# Power_Supply_2.net
KiCad netlist of a schematic drawn in Altium Designer
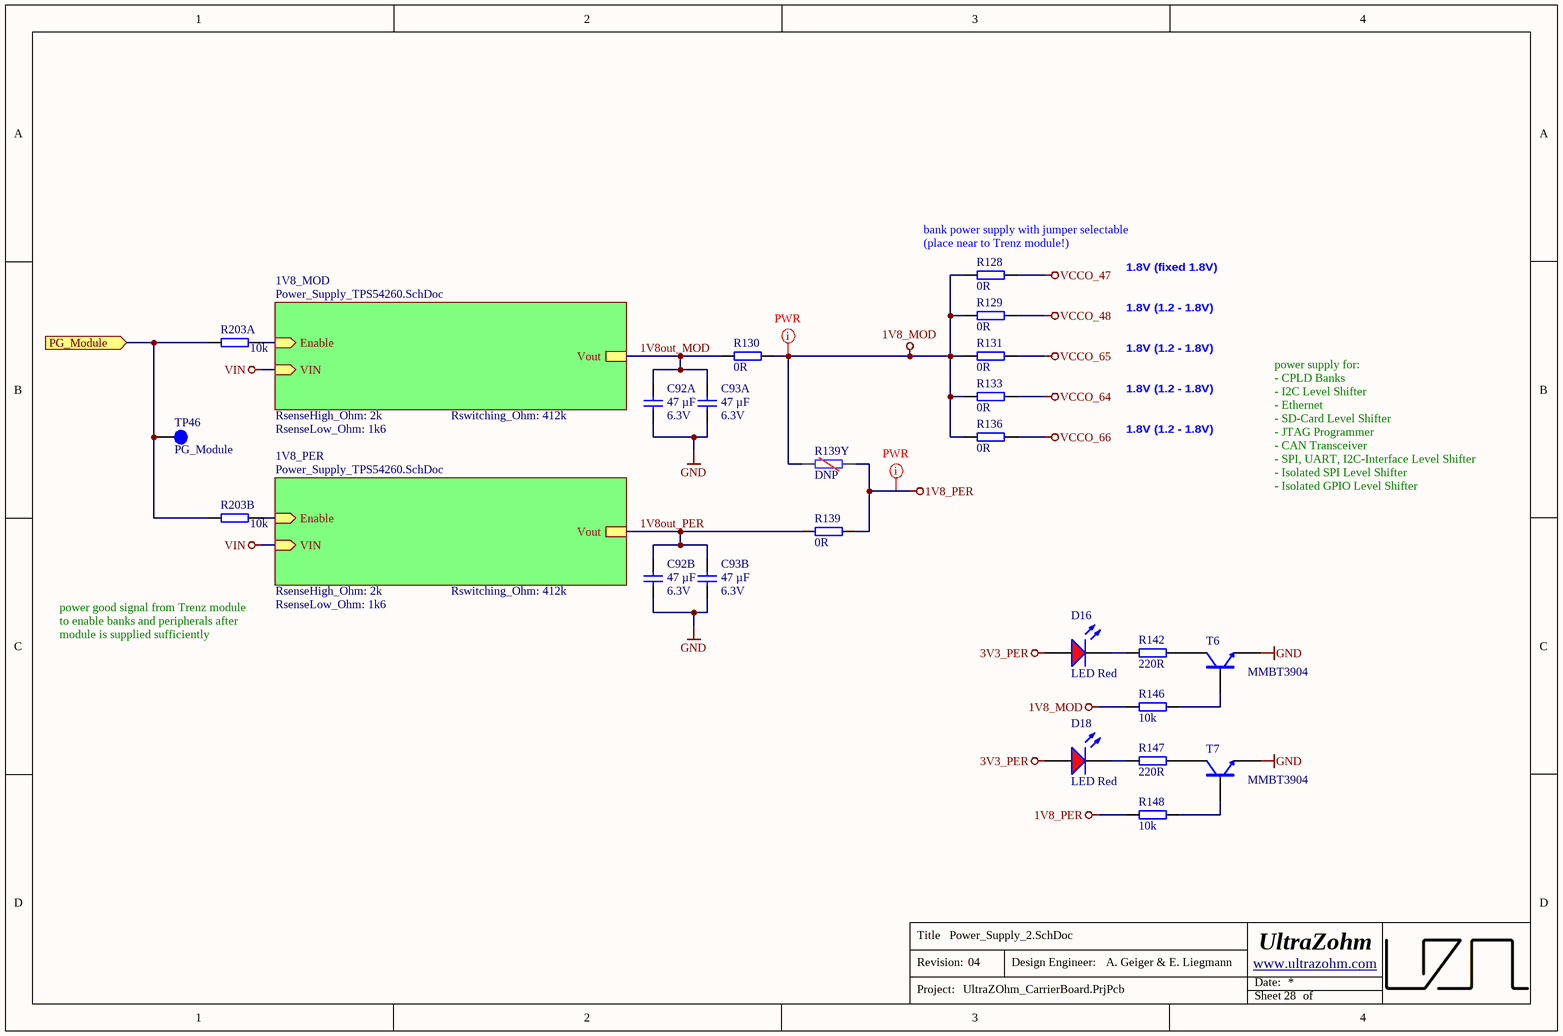
[diagram p0: Power_Supply_2.SchDoc]

(export (version "E")
  (design (tool "Eeschema 10.0.6"))
  (components
    (comp (ref "C92A")
      (value "47 µF")
      (footprint "C_0805_TE")
      (description "Generic capacitor")
      (fields
        (field (name "TOLERANCE") "10 %")
        (field (name "VOLTAGE") "6.3V")
        (field (name "MANUFACTURER PART NUMBER") "UZgen_C_0805_47uF_6.3V_X7R")
        (field (name "CREATED FROM") "UZgenTool")
      )
      (libsource (lib "user") (part "CAP-NP"))
    )
    (comp (ref "C92B")
      (value "47 µF")
      (footprint "C_0805_TE")
      (description "Generic capacitor")
      (fields
        (field (name "TOLERANCE") "10 %")
        (field (name "VOLTAGE") "6.3V")
        (field (name "MANUFACTURER PART NUMBER") "UZgen_C_0805_47uF_6.3V_X7R")
        (field (name "CREATED FROM") "UZgenTool")
      )
      (libsource (lib "user") (part "CAP-NP"))
    )
    (comp (ref "C93A")
      (value "47 µF")
      (footprint "C_0805_TE")
      (description "Generic capacitor")
      (fields
        (field (name "TOLERANCE") "10 %")
        (field (name "VOLTAGE") "6.3V")
        (field (name "MANUFACTURER PART NUMBER") "UZgen_C_0805_47uF_6.3V_X7R")
        (field (name "CREATED FROM") "UZgenTool")
      )
      (libsource (lib "user") (part "CAP-NP"))
    )
    (comp (ref "C93B")
      (value "47 µF")
      (footprint "C_0805_TE")
      (description "Generic capacitor")
      (fields
        (field (name "TOLERANCE") "10 %")
        (field (name "VOLTAGE") "6.3V")
        (field (name "MANUFACTURER PART NUMBER") "UZgen_C_0805_47uF_6.3V_X7R")
        (field (name "CREATED FROM") "UZgenTool")
      )
      (libsource (lib "user") (part "CAP-NP"))
    )
    (comp (ref "D16")
      (value "LED Red")
      (footprint "WL-SMCW_0603")
      (description "Standard LEDs - SMD 0603 red")
      (fields
        (field (name "MANUFACTURER PART NUMBER") "UZgen_LED_0603_Red")
        (field (name "MANUFACTURER") "UZgen")
        (field (name "CREATED FROM") "UZgenTool")
      )
      (libsource (lib "user") (part "LED_Red"))
    )
    (comp (ref "D18")
      (value "LED Red")
      (footprint "WL-SMCW_0603")
      (description "Standard LEDs - SMD 0603 red")
      (fields
        (field (name "MANUFACTURER PART NUMBER") "UZgen_LED_0603_Red")
        (field (name "MANUFACTURER") "UZgen")
        (field (name "CREATED FROM") "UZgenTool")
      )
      (libsource (lib "user") (part "LED_Red"))
    )
    (comp (ref "R128")
      (value "0R")
      (footprint "R_1206_TE")
      (description "Generic resistor")
      (fields
        (field (name "TOLERANCE") "1 %")
        (field (name "MANUFACTURER PART NUMBER") "UZgen_R_1206_0R")
        (field (name "CREATED FROM") "UZgenTool")
      )
      (libsource (lib "user") (part "RES"))
    )
    (comp (ref "R129")
      (value "0R")
      (footprint "R_1206_TE")
      (description "Generic resistor")
      (fields
        (field (name "TOLERANCE") "1 %")
        (field (name "MANUFACTURER PART NUMBER") "UZgen_R_1206_0R")
        (field (name "CREATED FROM") "UZgenTool")
      )
      (libsource (lib "user") (part "RES"))
    )
    (comp (ref "R130")
      (value "0R")
      (footprint "R_1206_TE")
      (description "Generic resistor")
      (fields
        (field (name "TOLERANCE") "1 %")
        (field (name "MANUFACTURER PART NUMBER") "UZgen_R_1206_0R")
        (field (name "CREATED FROM") "UZgenTool")
      )
      (libsource (lib "user") (part "RES"))
    )
    (comp (ref "R131")
      (value "0R")
      (footprint "R_1206_TE")
      (description "Generic resistor")
      (fields
        (field (name "TOLERANCE") "1 %")
        (field (name "MANUFACTURER PART NUMBER") "UZgen_R_1206_0R")
        (field (name "CREATED FROM") "UZgenTool")
      )
      (libsource (lib "user") (part "RES"))
    )
    (comp (ref "R133")
      (value "0R")
      (footprint "R_1206_TE")
      (description "Generic resistor")
      (fields
        (field (name "TOLERANCE") "1 %")
        (field (name "MANUFACTURER PART NUMBER") "UZgen_R_1206_0R")
        (field (name "CREATED FROM") "UZgenTool")
      )
      (libsource (lib "user") (part "RES"))
    )
    (comp (ref "R136")
      (value "0R")
      (footprint "R_1206_TE")
      (description "Generic resistor")
      (fields
        (field (name "TOLERANCE") "1 %")
        (field (name "MANUFACTURER PART NUMBER") "UZgen_R_1206_0R")
        (field (name "CREATED FROM") "UZgenTool")
      )
      (libsource (lib "user") (part "RES"))
    )
    (comp (ref "R139")
      (value "0R")
      (footprint "R_1206_TE")
      (description "Generic resistor")
      (fields
        (field (name "TOLERANCE") "1 %")
        (field (name "MANUFACTURER PART NUMBER") "UZgen_R_1206_0R")
        (field (name "CREATED FROM") "UZgenTool")
      )
      (libsource (lib "user") (part "RES"))
    )
    (comp (ref "R139Y")
      (value "DNP")
      (footprint "R_1206_TE-DNP")
      (description "Generic resistor (DNP)")
      (fields
        (field (name "MANUFACTURER PART NUMBER") "UZgen_R_1206_DNP")
        (field (name "MANUFACTURER") "UZgen")
        (field (name "CREATED FROM") "UZgenTool")
      )
      (libsource (lib "user") (part "RES-DNP"))
    )
    (comp (ref "R142")
      (value "220R")
      (footprint "R_0603_TE")
      (description "Generic resistor")
      (fields
        (field (name "TOLERANCE") "1 %")
        (field (name "MANUFACTURER PART NUMBER") "UZgen_R_0603_220R")
        (field (name "CREATED FROM") "UZgenTool")
      )
      (libsource (lib "user") (part "RES"))
    )
    (comp (ref "R146")
      (value "10k")
      (footprint "R_0603_TE")
      (description "Generic resistor")
      (fields
        (field (name "TOLERANCE") "1 %")
        (field (name "MANUFACTURER PART NUMBER") "UZgen_R_0603_10k")
        (field (name "CREATED FROM") "AGeiger")
      )
      (libsource (lib "user") (part "RES"))
    )
    (comp (ref "R147")
      (value "220R")
      (footprint "R_0603_TE")
      (description "Generic resistor")
      (fields
        (field (name "TOLERANCE") "1 %")
        (field (name "MANUFACTURER PART NUMBER") "UZgen_R_0603_220R")
        (field (name "CREATED FROM") "UZgenTool")
      )
      (libsource (lib "user") (part "RES"))
    )
    (comp (ref "R148")
      (value "10k")
      (footprint "R_0603_TE")
      (description "Generic resistor")
      (fields
        (field (name "TOLERANCE") "1 %")
        (field (name "MANUFACTURER PART NUMBER") "UZgen_R_0603_10k")
        (field (name "CREATED FROM") "AGeiger")
      )
      (libsource (lib "user") (part "RES"))
    )
    (comp (ref "R203A")
      (value "10k")
      (footprint "R_0603_TE")
      (description "Generic resistor")
      (fields
        (field (name "TOLERANCE") "1 %")
        (field (name "MANUFACTURER PART NUMBER") "UZgen_R_0603_10k")
        (field (name "CREATED FROM") "AGeiger")
      )
      (libsource (lib "user") (part "RES"))
    )
    (comp (ref "R203B")
      (value "10k")
      (footprint "R_0603_TE")
      (description "Generic resistor")
      (fields
        (field (name "TOLERANCE") "1 %")
        (field (name "MANUFACTURER PART NUMBER") "UZgen_R_0603_10k")
        (field (name "CREATED FROM") "AGeiger")
      )
      (libsource (lib "user") (part "RES"))
    )
    (comp (ref "T6")
      (value "MMBT3904")
      (footprint "SOT95P280X145-3N")
      (fields
        (field (name "MANUFACTURER") "Jiangsu Changjing Electronics Technology Co., Ltd.")
        (field (name "LCSC PART NUMBER") "C20526")
        (field (name "CREATED FROM") "NDiringer")
      )
      (libsource (lib "user") (part "NPN-SOT23"))
    )
    (comp (ref "T7")
      (value "MMBT3904")
      (footprint "SOT95P280X145-3N")
      (fields
        (field (name "MANUFACTURER") "Jiangsu Changjing Electronics Technology Co., Ltd.")
        (field (name "LCSC PART NUMBER") "C20526")
        (field (name "CREATED FROM") "NDiringer")
      )
      (libsource (lib "user") (part "NPN-SOT23"))
    )
    (comp (ref "TP46")
      (value "PG_Module")
      (footprint "TP_1mm")
      (description "Testpoint 1mm")
      (fields
        (field (name "MANUFACTURER PART NUMBER") "NULL")
        (field (name "CREATED") "2018_06_25_AGeiger")
        (field (name "CREATED FROM") "AGeiger")
      )
      (libsource (lib "user") (part "TP_1mm"))
    )
  )
  (nets
    (net (code "1") (name "/1V8out_MOD") (class "Default")
      (node (ref "C92A") (pin "2") (pinfunction "2_2") (pintype "passive"))
      (node (ref "C93A") (pin "2") (pinfunction "2_2") (pintype "passive"))
      (node (ref "R130") (pin "1") (pinfunction "1_1") (pintype "passive"))
    )
    (net (code "2") (name "/1V8out_PER") (class "Default")
      (node (ref "C92B") (pin "2") (pinfunction "2_2") (pintype "passive"))
      (node (ref "C93B") (pin "2") (pinfunction "2_2") (pintype "passive"))
      (node (ref "R139") (pin "1") (pinfunction "1_1") (pintype "passive"))
    )
    (net (code "3") (name "/Enable") (class "Default")
      (node (ref "R203A") (pin "2") (pinfunction "2_2") (pintype "passive"))
    )
    (net (code "4") (name "/Enable_1") (class "Default")
      (node (ref "R203B") (pin "2") (pinfunction "2_2") (pintype "passive"))
    )
    (net (code "5") (name "/PG_Module") (class "Default")
      (node (ref "R203A") (pin "1") (pinfunction "1_1") (pintype "passive"))
      (node (ref "R203B") (pin "1") (pinfunction "1_1") (pintype "passive"))
      (node (ref "TP46") (pin "1") (pintype "passive"))
    )
    (net (code "6") (name "1V8_MOD") (class "Default")
      (node (ref "R128") (pin "1") (pinfunction "1_1") (pintype "passive"))
      (node (ref "R129") (pin "1") (pinfunction "1_1") (pintype "passive"))
      (node (ref "R130") (pin "2") (pinfunction "2_2") (pintype "passive"))
      (node (ref "R131") (pin "1") (pinfunction "1_1") (pintype "passive"))
      (node (ref "R133") (pin "1") (pinfunction "1_1") (pintype "passive"))
      (node (ref "R136") (pin "1") (pinfunction "1_1") (pintype "passive"))
      (node (ref "R139Y") (pin "1") (pinfunction "1_1") (pintype "passive"))
      (node (ref "R146") (pin "1") (pinfunction "1_1") (pintype "passive"))
    )
    (net (code "7") (name "1V8_PER") (class "Default")
      (node (ref "R139") (pin "2") (pinfunction "2_2") (pintype "passive"))
      (node (ref "R139Y") (pin "2") (pinfunction "2_2") (pintype "passive"))
      (node (ref "R148") (pin "1") (pinfunction "1_1") (pintype "passive"))
    )
    (net (code "8") (name "3V3_PER") (class "Default")
      (node (ref "D16") (pin "2") (pinfunction "A_2") (pintype "passive"))
      (node (ref "D18") (pin "2") (pinfunction "A_2") (pintype "passive"))
    )
    (net (code "9") (name "GND") (class "Default")
      (node (ref "C92A") (pin "1") (pinfunction "1_1") (pintype "passive"))
      (node (ref "C92B") (pin "1") (pinfunction "1_1") (pintype "passive"))
      (node (ref "C93A") (pin "1") (pinfunction "1_1") (pintype "passive"))
      (node (ref "C93B") (pin "1") (pinfunction "1_1") (pintype "passive"))
      (node (ref "T6") (pin "2") (pinfunction "EMITTER_2") (pintype "passive"))
      (node (ref "T7") (pin "2") (pinfunction "EMITTER_2") (pintype "passive"))
    )
    (net (code "10") (name "Net-(D16-K)") (class "Default")
      (node (ref "D16") (pin "1") (pinfunction "K_1") (pintype "passive"))
      (node (ref "R142") (pin "1") (pinfunction "1_1") (pintype "passive"))
    )
    (net (code "11") (name "Net-(D18-K)") (class "Default")
      (node (ref "D18") (pin "1") (pinfunction "K_1") (pintype "passive"))
      (node (ref "R147") (pin "1") (pinfunction "1_1") (pintype "passive"))
    )
    (net (code "12") (name "Net-(T6-BASIS)") (class "Default")
      (node (ref "R146") (pin "2") (pinfunction "2_2") (pintype "passive"))
      (node (ref "T6") (pin "1") (pinfunction "BASIS_1") (pintype "passive"))
    )
    (net (code "13") (name "Net-(T6-COLLECTOR)") (class "Default")
      (node (ref "R142") (pin "2") (pinfunction "2_2") (pintype "passive"))
      (node (ref "T6") (pin "3") (pinfunction "COLLECTOR_3") (pintype "passive"))
    )
    (net (code "14") (name "Net-(T7-BASIS)") (class "Default")
      (node (ref "R148") (pin "2") (pinfunction "2_2") (pintype "passive"))
      (node (ref "T7") (pin "1") (pinfunction "BASIS_1") (pintype "passive"))
    )
    (net (code "15") (name "Net-(T7-COLLECTOR)") (class "Default")
      (node (ref "R147") (pin "2") (pinfunction "2_2") (pintype "passive"))
      (node (ref "T7") (pin "3") (pinfunction "COLLECTOR_3") (pintype "passive"))
    )
    (net (code "16") (name "VCCO_47") (class "Default")
      (node (ref "R128") (pin "2") (pinfunction "2_2") (pintype "passive"))
    )
    (net (code "17") (name "VCCO_48") (class "Default")
      (node (ref "R129") (pin "2") (pinfunction "2_2") (pintype "passive"))
    )
    (net (code "18") (name "VCCO_64") (class "Default")
      (node (ref "R133") (pin "2") (pinfunction "2_2") (pintype "passive"))
    )
    (net (code "19") (name "VCCO_65") (class "Default")
      (node (ref "R131") (pin "2") (pinfunction "2_2") (pintype "passive"))
    )
    (net (code "20") (name "VCCO_66") (class "Default")
      (node (ref "R136") (pin "2") (pinfunction "2_2") (pintype "passive"))
    )
  )
)
